# pH_v5_0.net
KiCad netlist of a schematic drawn in EAGLE
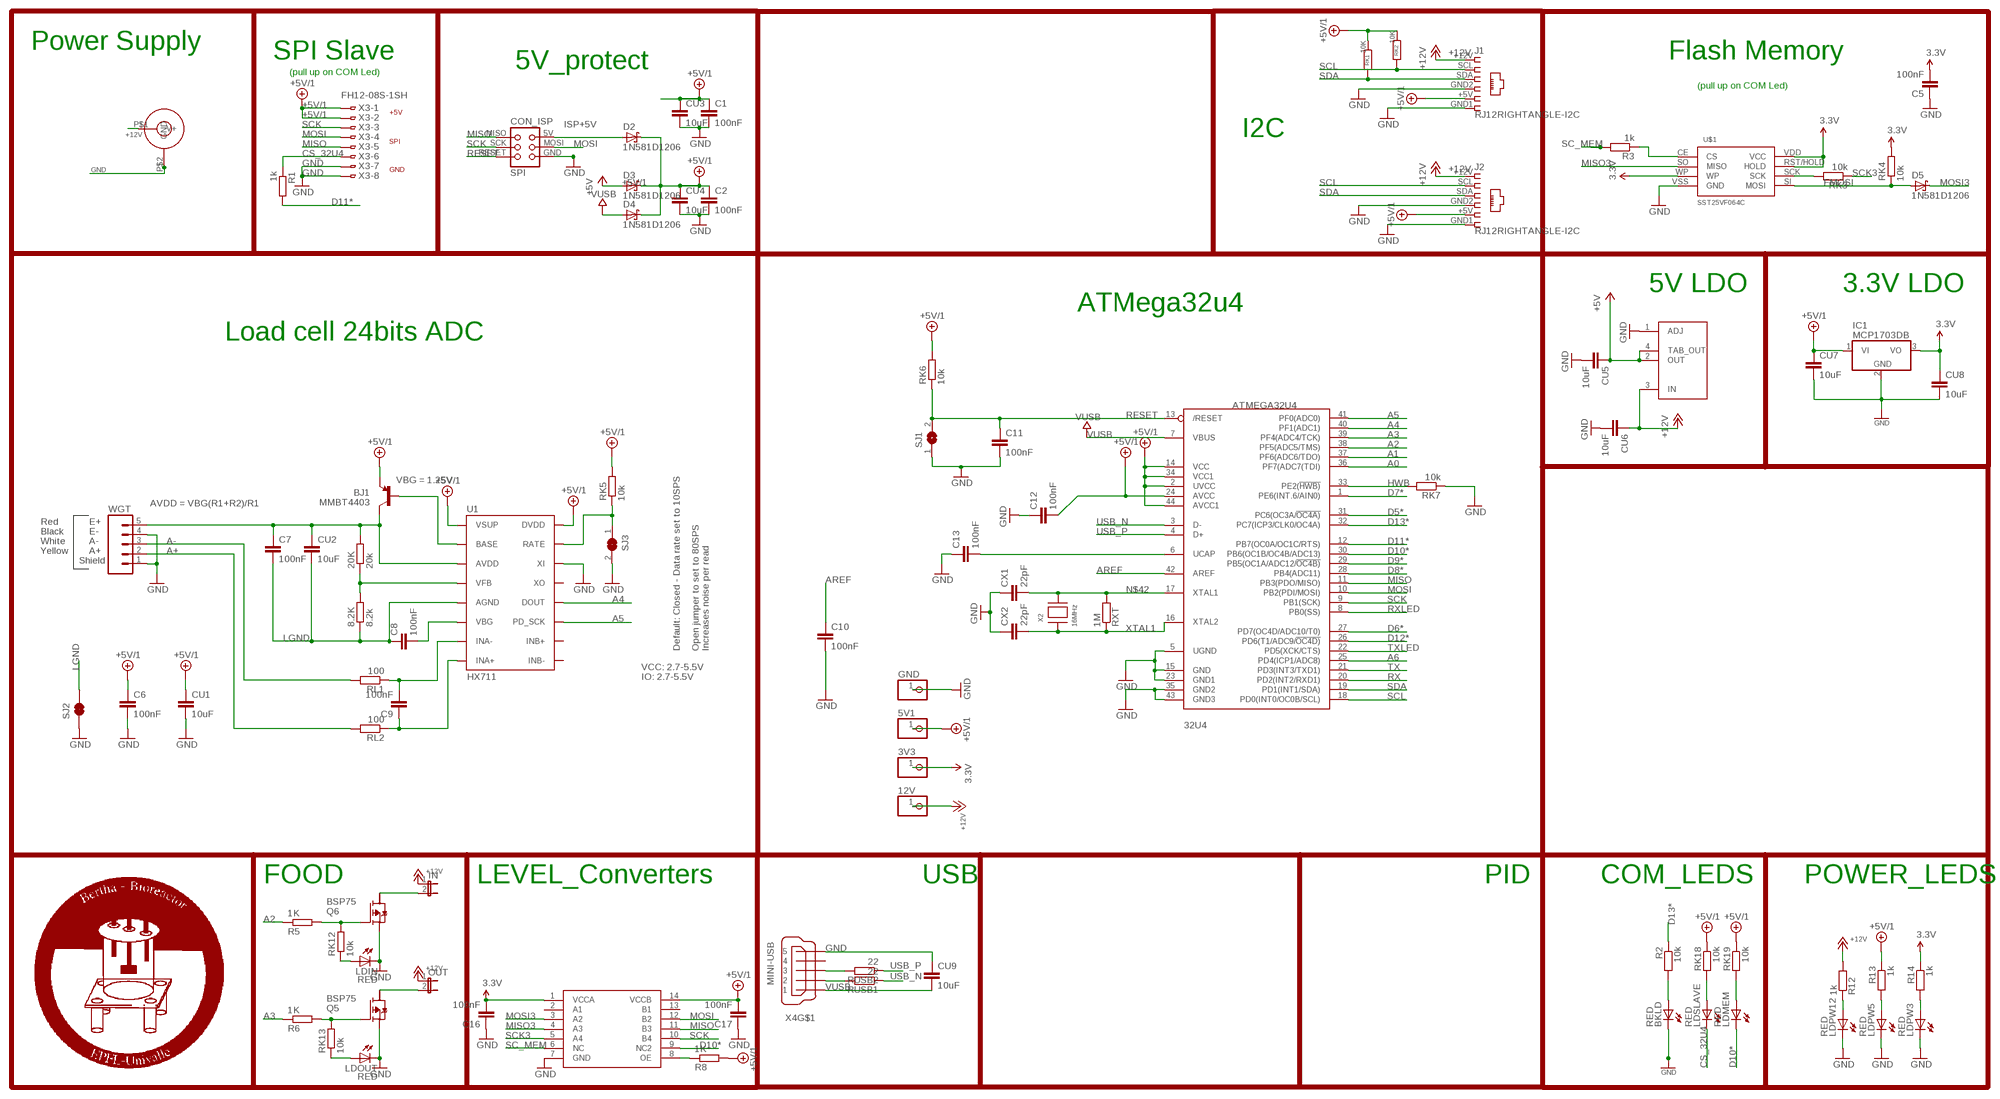
[diagram p0: schematic, sheet 1]

(export (version "E")
  (design (tool "Eeschema 10.0.6"))
  (components
    (comp (ref "3V3")
      (value "PINHD-1X1")
      (footprint "eagle-import:1X01")
      (libsource (lib "eagle-import") (part "PINHD-1X1"))
    )
    (comp (ref "5V1")
      (value "PINHD-1X1")
      (footprint "eagle-import:1X01")
      (libsource (lib "eagle-import") (part "PINHD-1X1"))
    )
    (comp (ref "8.2K")
      (value "8.2k")
      (footprint "eagle-import:M0805")
      (libsource (lib "eagle-import") (part "resistor_R-EU_M0805"))
    )
    (comp (ref "12V")
      (value "PINHD-1X1")
      (footprint "eagle-import:1X01")
      (libsource (lib "eagle-import") (part "PINHD-1X1"))
    )
    (comp (ref "20K")
      (value "20k")
      (footprint "eagle-import:M0805")
      (libsource (lib "eagle-import") (part "resistor_R-EU_M0805"))
    )
    (comp (ref "32U4")
      (value "ATMEGA32U4")
      (footprint "eagle-import:TQFP44")
      (libsource (lib "eagle-import") (part "ATMEGA32U4-AU"))
    )
    (comp (ref "BJ1")
      (value "MMBT4403")
      (footprint "eagle-import:SOT23-3")
      (libsource (lib "eagle-import") (part "TRANSISTOR_PNPMMBT4403"))
    )
    (comp (ref "BKLD")
      (value "RED")
      (footprint "eagle-import:CHIP-LED0805")
      (libsource (lib "eagle-import") (part "LEDCHIP-LED0805"))
    )
    (comp (ref "C1")
      (value "100nF")
      (footprint "eagle-import:C1206")
      (libsource (lib "eagle-import") (part "C-EUC1206"))
    )
    (comp (ref "C2")
      (value "100nF")
      (footprint "eagle-import:C1206")
      (libsource (lib "eagle-import") (part "C-EUC1206"))
    )
    (comp (ref "C5")
      (value "100nF")
      (footprint "eagle-import:C1206")
      (libsource (lib "eagle-import") (part "C-EUC1206"))
    )
    (comp (ref "C6")
      (value "100nF")
      (footprint "eagle-import:C1206")
      (libsource (lib "eagle-import") (part "C-EUC1206"))
    )
    (comp (ref "C7")
      (value "100nF")
      (footprint "eagle-import:C1206")
      (libsource (lib "eagle-import") (part "C-EUC1206"))
    )
    (comp (ref "C8")
      (value "100nF")
      (footprint "eagle-import:C1206")
      (libsource (lib "eagle-import") (part "C-EUC1206"))
    )
    (comp (ref "C9")
      (value "100nF")
      (footprint "eagle-import:C1206")
      (libsource (lib "eagle-import") (part "C-EUC1206"))
    )
    (comp (ref "C10")
      (value "100nF")
      (footprint "eagle-import:C1206")
      (libsource (lib "eagle-import") (part "C-EUC1206"))
    )
    (comp (ref "C11")
      (value "100nF")
      (footprint "eagle-import:C1206")
      (libsource (lib "eagle-import") (part "C-EUC1206"))
    )
    (comp (ref "C12")
      (value "100nF")
      (footprint "eagle-import:C1206")
      (libsource (lib "eagle-import") (part "C-EUC1206"))
    )
    (comp (ref "C13")
      (value "100nF")
      (footprint "eagle-import:C1206")
      (libsource (lib "eagle-import") (part "C-EUC1206"))
    )
    (comp (ref "C16")
      (value "100nF")
      (footprint "eagle-import:C1206")
      (libsource (lib "eagle-import") (part "C-EUC1206"))
    )
    (comp (ref "C17")
      (value "100nF")
      (footprint "eagle-import:C1206")
      (libsource (lib "eagle-import") (part "C-EUC1206"))
    )
    (comp (ref "CON1")
      (value "JACK_DC_BARREL")
      (footprint "eagle-import:DC_BARREL")
      (libsource (lib "eagle-import") (part "JACK_DC_BARREL"))
    )
    (comp (ref "CON_ISP")
      (value "SPI")
      (footprint "eagle-import:TC2030-MCP-NL")
      (libsource (lib "eagle-import") (part "TINYISPT"))
    )
    (comp (ref "CU1")
      (value "10uF")
      (footprint "eagle-import:C1206")
      (libsource (lib "eagle-import") (part "C-EUC1206"))
    )
    (comp (ref "CU2")
      (value "10uF")
      (footprint "eagle-import:C1206")
      (libsource (lib "eagle-import") (part "C-EUC1206"))
    )
    (comp (ref "CU3")
      (value "10uF")
      (footprint "eagle-import:C1206")
      (libsource (lib "eagle-import") (part "C-EUC1206"))
    )
    (comp (ref "CU4")
      (value "10uF")
      (footprint "eagle-import:C1206")
      (libsource (lib "eagle-import") (part "C-EUC1206"))
    )
    (comp (ref "CU5")
      (value "10uF")
      (footprint "eagle-import:C1206")
      (libsource (lib "eagle-import") (part "C-EUC1206"))
    )
    (comp (ref "CU6")
      (value "10uF")
      (footprint "eagle-import:C1206")
      (libsource (lib "eagle-import") (part "C-EUC1206"))
    )
    (comp (ref "CU7")
      (value "10uF")
      (footprint "eagle-import:C1206")
      (libsource (lib "eagle-import") (part "C-EUC1206"))
    )
    (comp (ref "CU8")
      (value "10uF")
      (footprint "eagle-import:C1206")
      (libsource (lib "eagle-import") (part "C-EUC1206"))
    )
    (comp (ref "CU9")
      (value "10uF")
      (footprint "eagle-import:C1206")
      (libsource (lib "eagle-import") (part "C-EUC1206"))
    )
    (comp (ref "CX1")
      (value "22pF")
      (footprint "eagle-import:C1206")
      (libsource (lib "eagle-import") (part "C-EUC1206"))
    )
    (comp (ref "CX2")
      (value "22pF")
      (footprint "eagle-import:C1206")
      (libsource (lib "eagle-import") (part "C-EUC1206"))
    )
    (comp (ref "D2")
      (value "1N581D1206")
      (footprint "eagle-import:LED-1206")
      (libsource (lib "eagle-import") (part "1N581D1206"))
    )
    (comp (ref "D3")
      (value "1N581D1206")
      (footprint "eagle-import:LED-1206")
      (libsource (lib "eagle-import") (part "1N581D1206"))
    )
    (comp (ref "D4")
      (value "1N581D1206")
      (footprint "eagle-import:LED-1206")
      (libsource (lib "eagle-import") (part "1N581D1206"))
    )
    (comp (ref "D5")
      (value "1N581D1206")
      (footprint "eagle-import:LED-1206")
      (libsource (lib "eagle-import") (part "1N581D1206"))
    )
    (comp (ref "GND")
      (value "PINHD-1X1")
      (footprint "eagle-import:1X01")
      (libsource (lib "eagle-import") (part "PINHD-1X1"))
    )
    (comp (ref "IC1")
      (value "MCP1703DB")
      (footprint "eagle-import:SOT223")
      (libsource (lib "eagle-import") (part "MCP1703DB"))
    )
    (comp (ref "IN")
      (value "JP1E")
      (footprint "eagle-import:JP1")
      (libsource (lib "eagle-import") (part "JP1E"))
    )
    (comp (ref "J1")
      (value "RJ12RIGHTANGLE-I2C")
      (footprint "eagle-import:RJ12-RIGHTANGLE-I2C")
      (libsource (lib "eagle-import") (part "RJ12RIGHTANGLE-I2C"))
    )
    (comp (ref "J2")
      (value "RJ12RIGHTANGLE-I2C")
      (footprint "eagle-import:RJ12-RIGHTANGLE-I2C")
      (libsource (lib "eagle-import") (part "RJ12RIGHTANGLE-I2C"))
    )
    (comp (ref "LDIN")
      (value "RED")
      (footprint "eagle-import:CHIP-LED0805")
      (libsource (lib "eagle-import") (part "LEDCHIP-LED0805"))
    )
    (comp (ref "LDMEM")
      (value "RED")
      (footprint "eagle-import:CHIP-LED0805")
      (libsource (lib "eagle-import") (part "LEDCHIP-LED0805"))
    )
    (comp (ref "LDOUT")
      (value "RED")
      (footprint "eagle-import:CHIP-LED0805")
      (libsource (lib "eagle-import") (part "LEDCHIP-LED0805"))
    )
    (comp (ref "LDPW3")
      (value "RED")
      (footprint "eagle-import:CHIP-LED0805")
      (libsource (lib "eagle-import") (part "LEDCHIP-LED0805"))
    )
    (comp (ref "LDPW5")
      (value "RED")
      (footprint "eagle-import:CHIP-LED0805")
      (libsource (lib "eagle-import") (part "LEDCHIP-LED0805"))
    )
    (comp (ref "LDPW12")
      (value "RED")
      (footprint "eagle-import:CHIP-LED0805")
      (libsource (lib "eagle-import") (part "LEDCHIP-LED0805"))
    )
    (comp (ref "LDSLAVE")
      (value "RED")
      (footprint "eagle-import:CHIP-LED0805")
      (libsource (lib "eagle-import") (part "LEDCHIP-LED0805"))
    )
    (comp (ref "OUT")
      (value "JP1E")
      (footprint "eagle-import:JP1")
      (libsource (lib "eagle-import") (part "JP1E"))
    )
    (comp (ref "Q5")
      (value "BSP75")
      (footprint "eagle-import:PG-SOT-223")
      (libsource (lib "eagle-import") (part "BSP613P"))
    )
    (comp (ref "Q6")
      (value "BSP75")
      (footprint "eagle-import:PG-SOT-223")
      (libsource (lib "eagle-import") (part "BSP613P"))
    )
    (comp (ref "R1")
      (value "1k")
      (footprint "eagle-import:R0805")
      (libsource (lib "eagle-import") (part "R-EU_R0805"))
    )
    (comp (ref "R2")
      (value "10k")
      (footprint "eagle-import:R0805")
      (libsource (lib "eagle-import") (part "R-EU_R0805"))
    )
    (comp (ref "R3")
      (value "1k")
      (footprint "eagle-import:R0805")
      (libsource (lib "eagle-import") (part "R-EU_R0805"))
    )
    (comp (ref "R5")
      (value "1K")
      (footprint "eagle-import:R0805")
      (libsource (lib "eagle-import") (part "R-EU_R0805"))
    )
    (comp (ref "R6")
      (value "1K")
      (footprint "eagle-import:R0805")
      (libsource (lib "eagle-import") (part "R-EU_R0805"))
    )
    (comp (ref "R8")
      (value "1K")
      (footprint "eagle-import:R0805")
      (libsource (lib "eagle-import") (part "R-EU_R0805"))
    )
    (comp (ref "R12")
      (value "1k")
      (footprint "eagle-import:R0805")
      (libsource (lib "eagle-import") (part "R-EU_R0805"))
    )
    (comp (ref "R13")
      (value "1k")
      (footprint "eagle-import:R0805")
      (libsource (lib "eagle-import") (part "resistor_R-EU_R0805"))
    )
    (comp (ref "R14")
      (value "1k")
      (footprint "eagle-import:R0805")
      (libsource (lib "eagle-import") (part "resistor_R-EU_R0805"))
    )
    (comp (ref "RK1")
      (value "10K")
      (footprint "eagle-import:M0805")
      (libsource (lib "eagle-import") (part "resistor_R-EU_M0805"))
    )
    (comp (ref "RK2")
      (value "10K")
      (footprint "eagle-import:M0805")
      (libsource (lib "eagle-import") (part "resistor_R-EU_M0805"))
    )
    (comp (ref "RK3")
      (value "10k")
      (footprint "eagle-import:R0805")
      (libsource (lib "eagle-import") (part "R-EU_R0805"))
    )
    (comp (ref "RK4")
      (value "10k")
      (footprint "eagle-import:R0805")
      (libsource (lib "eagle-import") (part "R-EU_R0805"))
    )
    (comp (ref "RK5")
      (value "10k")
      (footprint "eagle-import:M0805")
      (libsource (lib "eagle-import") (part "resistor_R-EU_M0805"))
    )
    (comp (ref "RK6")
      (value "10k")
      (footprint "eagle-import:M0805")
      (libsource (lib "eagle-import") (part "resistor_R-EU_M0805"))
    )
    (comp (ref "RK7")
      (value "10k")
      (footprint "eagle-import:M0805")
      (libsource (lib "eagle-import") (part "resistor_R-EU_M0805"))
    )
    (comp (ref "RK12")
      (value "10k")
      (footprint "eagle-import:R0805")
      (libsource (lib "eagle-import") (part "R-EU_R0805"))
    )
    (comp (ref "RK13")
      (value "10k")
      (footprint "eagle-import:R0805")
      (libsource (lib "eagle-import") (part "R-EU_R0805"))
    )
    (comp (ref "RK18")
      (value "10k")
      (footprint "eagle-import:R0805")
      (libsource (lib "eagle-import") (part "R-EU_R0805"))
    )
    (comp (ref "RK19")
      (value "10k")
      (footprint "eagle-import:R0805")
      (libsource (lib "eagle-import") (part "R-EU_R0805"))
    )
    (comp (ref "RL1")
      (value "100")
      (footprint "eagle-import:M0805")
      (libsource (lib "eagle-import") (part "resistor_R-EU_M0805"))
    )
    (comp (ref "RL2")
      (value "100")
      (footprint "eagle-import:M0805")
      (libsource (lib "eagle-import") (part "resistor_R-EU_M0805"))
    )
    (comp (ref "RUSB1")
      (value "22")
      (footprint "eagle-import:M1206")
      (libsource (lib "eagle-import") (part "resistor_R-EU_M1206"))
    )
    (comp (ref "RUSB2")
      (value "22")
      (footprint "eagle-import:M1206")
      (libsource (lib "eagle-import") (part "resistor_R-EU_M1206"))
    )
    (comp (ref "RXT")
      (value "1M")
      (footprint "eagle-import:R0805")
      (libsource (lib "eagle-import") (part "R-EU_R0805"))
    )
    (comp (ref "SJ1") (value "SJ") (footprint "eagle-import:SJ") (libsource (lib "eagle-import") (part "SJ")))
    (comp (ref "SJ2")
      (value "JUMPER-PAD-2-NC_BY_TRACE")
      (footprint "eagle-import:PAD-JUMPER-2-NC_BY_TRACE_YES_SILK")
      (libsource (lib "eagle-import") (part "JUMPER-PAD-2-NC_BY_TRACE"))
    )
    (comp (ref "SJ3") (value "SJ") (footprint "eagle-import:SJ") (libsource (lib "eagle-import") (part "SJ")))
    (comp (ref "U$1")
      (value "SST25VF064C")
      (footprint "eagle-import:SOIC_8-LEAD")
      (libsource (lib "eagle-import") (part "SST25VF064C"))
    )
    (comp (ref "U$2")
      (value "NCP1117LPST50T3G")
      (footprint "eagle-import:SOT223")
      (libsource (lib "eagle-import") (part "NCP1117LPST50T3G"))
    )
    (comp (ref "U$6")
      (value "TXB0104")
      (footprint "eagle-import:SO14")
      (libsource (lib "eagle-import") (part "TXB0104"))
    )
    (comp (ref "U1")
      (value "HX711")
      (footprint "eagle-import:SO16")
      (libsource (lib "eagle-import") (part "HX711HX711"))
    )
    (comp (ref "WGT")
      (value "M05PTH")
      (footprint "eagle-import:1X05")
      (libsource (lib "eagle-import") (part "M05PTH"))
    )
    (comp (ref "X2")
      (value "16MHz")
      (footprint "eagle-import:NX6035")
      (libsource (lib "eagle-import") (part "XTALNX6035"))
    )
    (comp (ref "X3")
      (value "FH12-08S-1SH")
      (footprint "eagle-import:FH12-08S-1SH")
      (libsource (lib "eagle-import") (part "FH12-08S-1SH"))
    )
    (comp (ref "X4")
      (value "MINI-USB")
      (footprint "eagle-import:32005-201")
      (libsource (lib "eagle-import") (part "MINI-USB-SCHIELD-32005-201"))
    )
  )
  (nets
    (net (code "1") (name "+5V") (class "Default")
      (node (ref "CU5") (pin "1") (pinfunction "1_1") (pintype "passive"))
      (node (ref "D3") (pin "A") (pinfunction "A_A") (pintype "passive"))
      (node (ref "U$2") (pin "2") (pinfunction "OUT_2") (pintype "bidirectional"))
      (node (ref "U$2") (pin "4") (pinfunction "TAB_OUT_4") (pintype "bidirectional"))
    )
    (net (code "2") (name "+5V{slash}1") (class "Default")
      (node (ref "32U4") (pin "14") (pinfunction "VCC_14") (pintype "bidirectional"))
      (node (ref "32U4") (pin "2") (pinfunction "UVCC_2") (pintype "bidirectional"))
      (node (ref "32U4") (pin "24") (pinfunction "AVCC_24") (pintype "bidirectional"))
      (node (ref "32U4") (pin "34") (pinfunction "VCC1_34") (pintype "bidirectional"))
      (node (ref "32U4") (pin "44") (pinfunction "AVCC1_44") (pintype "bidirectional"))
      (node (ref "5V1") (pin "1") (pinfunction "1_1") (pintype "passive"))
      (node (ref "BJ1") (pin "2") (pinfunction "E_2") (pintype "passive"))
      (node (ref "C1") (pin "1") (pinfunction "1_1") (pintype "passive"))
      (node (ref "C12") (pin "2") (pinfunction "2_2") (pintype "passive"))
      (node (ref "C17") (pin "2") (pinfunction "2_2") (pintype "passive"))
      (node (ref "C2") (pin "1") (pinfunction "1_1") (pintype "passive"))
      (node (ref "C6") (pin "1") (pinfunction "1_1") (pintype "passive"))
      (node (ref "CU1") (pin "1") (pinfunction "1_1") (pintype "passive"))
      (node (ref "CU3") (pin "1") (pinfunction "1_1") (pintype "passive"))
      (node (ref "CU4") (pin "1") (pinfunction "1_1") (pintype "passive"))
      (node (ref "CU7") (pin "1") (pinfunction "1_1") (pintype "passive"))
      (node (ref "D2") (pin "C") (pinfunction "C_C") (pintype "passive"))
      (node (ref "D3") (pin "C") (pinfunction "C_C") (pintype "passive"))
      (node (ref "D4") (pin "C") (pinfunction "C_C") (pintype "passive"))
      (node (ref "IC1") (pin "1") (pinfunction "VI_1") (pintype "input"))
      (node (ref "J1") (pin "+5V") (pinfunction "5_+5V") (pintype "power_in"))
      (node (ref "J2") (pin "+5V") (pinfunction "5_+5V") (pintype "power_in"))
      (node (ref "R13") (pin "1") (pinfunction "1_1") (pintype "passive"))
      (node (ref "R8") (pin "2") (pinfunction "2_2") (pintype "passive"))
      (node (ref "RK1") (pin "1") (pinfunction "1_1") (pintype "passive"))
      (node (ref "RK18") (pin "1") (pinfunction "1_1") (pintype "passive"))
      (node (ref "RK19") (pin "1") (pinfunction "1_1") (pintype "passive"))
      (node (ref "RK2") (pin "1") (pinfunction "1_1") (pintype "passive"))
      (node (ref "RK5") (pin "2") (pinfunction "2_2") (pintype "passive"))
      (node (ref "RK6") (pin "2") (pinfunction "2_2") (pintype "passive"))
      (node (ref "U$6") (pin "14") (pinfunction "VCCB_14") (pintype "bidirectional"))
      (node (ref "U1") (pin "1") (pinfunction "VSUP_1") (pintype "bidirectional"))
      (node (ref "U1") (pin "16") (pinfunction "DVDD_16") (pintype "bidirectional"))
      (node (ref "X3") (pin "1") (pinfunction "1_1") (pintype "passive"))
      (node (ref "X3") (pin "2") (pinfunction "1_2") (pintype "passive"))
    )
    (net (code "3") (name "+12V") (class "Default")
      (node (ref "12V") (pin "1") (pinfunction "1_1") (pintype "passive"))
      (node (ref "CON1") (pin "P$1") (pinfunction "V+_P$1") (pintype "bidirectional"))
      (node (ref "CU6") (pin "1") (pinfunction "1_1") (pintype "passive"))
      (node (ref "IN") (pin "1") (pinfunction "1_1") (pintype "passive"))
      (node (ref "J1") (pin "+12V") (pinfunction "1_+12V") (pintype "power_in"))
      (node (ref "J2") (pin "+12V") (pinfunction "1_+12V") (pintype "power_in"))
      (node (ref "OUT") (pin "1") (pinfunction "1_1") (pintype "passive"))
      (node (ref "R12") (pin "2") (pinfunction "2_2") (pintype "passive"))
      (node (ref "U$2") (pin "3") (pinfunction "IN_3") (pintype "bidirectional"))
    )
    (net (code "4") (name "/A+") (class "Default")
      (node (ref "RL2") (pin "2") (pinfunction "2_2") (pintype "passive"))
      (node (ref "WGT") (pin "2") (pinfunction "2_2") (pintype "passive"))
    )
    (net (code "5") (name "/A-") (class "Default")
      (node (ref "RL1") (pin "2") (pinfunction "2_2") (pintype "passive"))
      (node (ref "WGT") (pin "3") (pinfunction "3_3") (pintype "passive"))
    )
    (net (code "6") (name "/A0") (class "Default")
      (node (ref "32U4") (pin "36") (pinfunction "PF7(ADC7(TDI)_36") (pintype "bidirectional"))
    )
    (net (code "7") (name "/A1") (class "Default")
      (node (ref "32U4") (pin "37") (pinfunction "PF6(ADC6/TDO)_37") (pintype "bidirectional"))
    )
    (net (code "8") (name "/A2") (class "Default")
      (node (ref "32U4") (pin "38") (pinfunction "PF5(ADC5/TMS)_38") (pintype "bidirectional"))
      (node (ref "R5") (pin "1") (pinfunction "1_1") (pintype "passive"))
    )
    (net (code "9") (name "/A3") (class "Default")
      (node (ref "32U4") (pin "39") (pinfunction "PF4(ADC4/TCK)_39") (pintype "bidirectional"))
      (node (ref "R6") (pin "1") (pinfunction "1_1") (pintype "passive"))
    )
    (net (code "10") (name "/A4") (class "Default")
      (node (ref "32U4") (pin "40") (pinfunction "PF1(ADC1)_40") (pintype "bidirectional"))
      (node (ref "U1") (pin "12") (pinfunction "DOUT_12") (pintype "bidirectional"))
    )
    (net (code "11") (name "/A5") (class "Default")
      (node (ref "32U4") (pin "41") (pinfunction "PF0(ADC0)_41") (pintype "bidirectional"))
      (node (ref "U1") (pin "11") (pinfunction "PD_SCK_11") (pintype "bidirectional"))
    )
    (net (code "12") (name "/A6") (class "Default")
      (node (ref "32U4") (pin "25") (pinfunction "PD4(ICP1/ADC8)_25") (pintype "bidirectional"))
    )
    (net (code "13") (name "/AREF") (class "Default")
      (node (ref "32U4") (pin "42") (pinfunction "AREF_42") (pintype "bidirectional"))
      (node (ref "C10") (pin "1") (pinfunction "1_1") (pintype "passive"))
    )
    (net (code "14") (name "/CS_32U4") (class "Default")
      (node (ref "LDSLAVE") (pin "C") (pinfunction "C_C") (pintype "passive"))
      (node (ref "R1") (pin "1") (pinfunction "1_1") (pintype "passive"))
      (node (ref "X3") (pin "6") (pinfunction "1_6") (pintype "passive"))
    )
    (net (code "15") (name "/D5*") (class "Default")
      (node (ref "32U4") (pin "31") (pinfunction "PC6(OC3A/~{OC4A})_31") (pintype "bidirectional"))
    )
    (net (code "16") (name "/D6*") (class "Default")
      (node (ref "32U4") (pin "27") (pinfunction "PD7(OC4D/ADC10/T0)_27") (pintype "bidirectional"))
    )
    (net (code "17") (name "/D7*") (class "Default")
      (node (ref "32U4") (pin "1") (pinfunction "PE6(INT.6/AIN0)_1") (pintype "bidirectional"))
    )
    (net (code "18") (name "/D8*") (class "Default")
      (node (ref "32U4") (pin "28") (pinfunction "PB4(ADC11)_28") (pintype "bidirectional"))
    )
    (net (code "19") (name "/D9*") (class "Default")
      (node (ref "32U4") (pin "29") (pinfunction "PB5(OC1A/ADC12/~{OC4B})_29") (pintype "bidirectional"))
    )
    (net (code "20") (name "/D10*") (class "Default")
      (node (ref "32U4") (pin "30") (pinfunction "PB6(OC1B/OC4B/ADC13)_30") (pintype "bidirectional"))
      (node (ref "LDMEM") (pin "C") (pinfunction "C_C") (pintype "passive"))
      (node (ref "U$6") (pin "9") (pinfunction "NC2_9") (pintype "bidirectional"))
    )
    (net (code "21") (name "/D11*") (class "Default")
      (node (ref "32U4") (pin "12") (pinfunction "PB7(OC0A/OC1C/RTS)_12") (pintype "bidirectional"))
      (node (ref "R1") (pin "2") (pinfunction "2_2") (pintype "passive"))
    )
    (net (code "22") (name "/D12*") (class "Default")
      (node (ref "32U4") (pin "26") (pinfunction "PD6(T1/ADC9/~{OC4D})_26") (pintype "bidirectional"))
    )
    (net (code "23") (name "/D13*") (class "Default")
      (node (ref "32U4") (pin "32") (pinfunction "PC7(ICP3/CLK0/OC4A)_32") (pintype "bidirectional"))
      (node (ref "R2") (pin "1") (pinfunction "1_1") (pintype "passive"))
    )
    (net (code "24") (name "/FMOSI") (class "Default")
      (node (ref "D5") (pin "A") (pinfunction "A_A") (pintype "passive"))
      (node (ref "RK4") (pin "1") (pinfunction "1_1") (pintype "passive"))
      (node (ref "U$1") (pin "SI") (pinfunction "MOSI_SI") (pintype "bidirectional"))
    )
    (net (code "25") (name "/HWB") (class "Default")
      (node (ref "32U4") (pin "33") (pinfunction "PE2(~{HWB})_33") (pintype "bidirectional"))
      (node (ref "RK7") (pin "2") (pinfunction "2_2") (pintype "passive"))
    )
    (net (code "26") (name "/ISP+5V") (class "Default")
      (node (ref "CON_ISP") (pin "5V") (pinfunction "VCC_5V") (pintype "passive"))
      (node (ref "D2") (pin "A") (pinfunction "A_A") (pintype "passive"))
    )
    (net (code "27") (name "/LGND") (class "Default")
      (node (ref "8.2K") (pin "1") (pinfunction "1_1") (pintype "passive"))
      (node (ref "C7") (pin "2") (pinfunction "2_2") (pintype "passive"))
      (node (ref "C8") (pin "1") (pinfunction "1_1") (pintype "passive"))
      (node (ref "CU2") (pin "2") (pinfunction "2_2") (pintype "passive"))
      (node (ref "SJ2") (pin "2") (pinfunction "2_2") (pintype "passive"))
      (node (ref "U1") (pin "5") (pinfunction "AGND_5") (pintype "bidirectional"))
    )
    (net (code "28") (name "/MISO") (class "Default")
      (node (ref "32U4") (pin "11") (pinfunction "PB3(PDO/MISO)_11") (pintype "bidirectional"))
      (node (ref "CON_ISP") (pin "MISO") (pinfunction "MISO_MISO") (pintype "passive"))
      (node (ref "U$6") (pin "11") (pinfunction "B3_11") (pintype "bidirectional"))
      (node (ref "X3") (pin "5") (pinfunction "1_5") (pintype "passive"))
    )
    (net (code "29") (name "/MISO3") (class "Default")
      (node (ref "U$1") (pin "SO") (pinfunction "MISO_SO") (pintype "bidirectional"))
      (node (ref "U$6") (pin "4") (pinfunction "A3_4") (pintype "bidirectional"))
    )
    (net (code "30") (name "/MOSI") (class "Default")
      (node (ref "32U4") (pin "10") (pinfunction "PB2(PDI/MOSI)_10") (pintype "bidirectional"))
      (node (ref "CON_ISP") (pin "MOSI") (pinfunction "MOSI_MOSI") (pintype "passive"))
      (node (ref "U$6") (pin "12") (pinfunction "B2_12") (pintype "bidirectional"))
      (node (ref "X3") (pin "4") (pinfunction "1_4") (pintype "passive"))
    )
    (net (code "31") (name "/MOSI3") (class "Default")
      (node (ref "D5") (pin "C") (pinfunction "C_C") (pintype "passive"))
      (node (ref "U$6") (pin "3") (pinfunction "A2_3") (pintype "bidirectional"))
    )
    (net (code "32") (name "/N$42") (class "Default")
      (node (ref "32U4") (pin "17") (pinfunction "XTAL1_17") (pintype "bidirectional"))
      (node (ref "CX1") (pin "2") (pinfunction "2_2") (pintype "passive"))
      (node (ref "RXT") (pin "2") (pinfunction "2_2") (pintype "passive"))
      (node (ref "X2") (pin "P$2") (pinfunction "P$2_P$2") (pintype "bidirectional"))
    )
    (net (code "33") (name "/RESET") (class "Default")
      (node (ref "32U4") (pin "13") (pinfunction "/RESET_13") (pintype "bidirectional"))
      (node (ref "C11") (pin "1") (pinfunction "1_1") (pintype "passive"))
      (node (ref "CON_ISP") (pin "RESET") (pinfunction "RESET_RESET") (pintype "passive"))
      (node (ref "RK6") (pin "1") (pinfunction "1_1") (pintype "passive"))
      (node (ref "SJ1") (pin "2") (pinfunction "2_2") (pintype "passive"))
    )
    (net (code "34") (name "/RX") (class "Default")
      (node (ref "32U4") (pin "20") (pinfunction "PD2(INT2/RXD1)_20") (pintype "bidirectional"))
    )
    (net (code "35") (name "/RXLED") (class "Default")
      (node (ref "32U4") (pin "8") (pinfunction "PB0(SS)_8") (pintype "bidirectional"))
    )
    (net (code "36") (name "/SCK") (class "Default")
      (node (ref "32U4") (pin "9") (pinfunction "PB1(SCK)_9") (pintype "bidirectional"))
      (node (ref "CON_ISP") (pin "SCK") (pinfunction "SCK_SCK") (pintype "passive"))
      (node (ref "U$6") (pin "10") (pinfunction "B4_10") (pintype "bidirectional"))
      (node (ref "X3") (pin "3") (pinfunction "1_3") (pintype "passive"))
    )
    (net (code "37") (name "/SCK3") (class "Default")
      (node (ref "RK3") (pin "1") (pinfunction "1_1") (pintype "passive"))
      (node (ref "U$6") (pin "5") (pinfunction "A4_5") (pintype "bidirectional"))
    )
    (net (code "38") (name "/SCL") (class "Default")
      (node (ref "32U4") (pin "18") (pinfunction "PD0(INT0/OC0B/SCL)_18") (pintype "bidirectional"))
      (node (ref "J1") (pin "SCL") (pinfunction "2_SCL") (pintype "bidirectional"))
      (node (ref "J2") (pin "SCL") (pinfunction "2_SCL") (pintype "bidirectional"))
      (node (ref "RK2") (pin "2") (pinfunction "2_2") (pintype "passive"))
    )
    (net (code "39") (name "/SC_MEM") (class "Default")
      (node (ref "R3") (pin "2") (pinfunction "2_2") (pintype "passive"))
      (node (ref "U$6") (pin "6") (pinfunction "NC_6") (pintype "bidirectional"))
    )
    (net (code "40") (name "/SDA") (class "Default")
      (node (ref "32U4") (pin "19") (pinfunction "PD1(INT1/SDA)_19") (pintype "bidirectional"))
      (node (ref "J1") (pin "SDA") (pinfunction "3_SDA") (pintype "bidirectional"))
      (node (ref "J2") (pin "SDA") (pinfunction "3_SDA") (pintype "bidirectional"))
      (node (ref "RK1") (pin "2") (pinfunction "2_2") (pintype "passive"))
    )
    (net (code "41") (name "/TX") (class "Default")
      (node (ref "32U4") (pin "21") (pinfunction "PD3(INT3/TXD1)_21") (pintype "bidirectional"))
    )
    (net (code "42") (name "/TXLED") (class "Default")
      (node (ref "32U4") (pin "22") (pinfunction "PD5(XCK/CTS)_22") (pintype "bidirectional"))
    )
    (net (code "43") (name "/USB_N") (class "Default")
      (node (ref "32U4") (pin "3") (pinfunction "D-_3") (pintype "bidirectional"))
      (node (ref "RUSB1") (pin "1") (pinfunction "1_1") (pintype "passive"))
    )
    (net (code "44") (name "/USB_P") (class "Default")
      (node (ref "32U4") (pin "4") (pinfunction "D+_4") (pintype "bidirectional"))
      (node (ref "RUSB2") (pin "1") (pinfunction "1_1") (pintype "passive"))
    )
    (net (code "45") (name "/XTAL1") (class "Default")
      (node (ref "32U4") (pin "16") (pinfunction "XTAL2_16") (pintype "bidirectional"))
      (node (ref "CX2") (pin "2") (pinfunction "2_2") (pintype "passive"))
      (node (ref "RXT") (pin "1") (pinfunction "1_1") (pintype "passive"))
      (node (ref "X2") (pin "P$1") (pinfunction "P$1_P$1") (pintype "bidirectional"))
    )
    (net (code "46") (name "3.3V") (class "Default")
      (node (ref "3V3") (pin "1") (pinfunction "1_1") (pintype "passive"))
      (node (ref "C16") (pin "2") (pinfunction "2_2") (pintype "passive"))
      (node (ref "C5") (pin "2") (pinfunction "2_2") (pintype "passive"))
      (node (ref "CU8") (pin "1") (pinfunction "1_1") (pintype "passive"))
      (node (ref "IC1") (pin "3") (pinfunction "VO_3") (pintype "passive"))
      (node (ref "R14") (pin "1") (pinfunction "1_1") (pintype "passive"))
      (node (ref "RK4") (pin "2") (pinfunction "2_2") (pintype "passive"))
      (node (ref "U$1") (pin "RST/HOLD") (pinfunction "HOLD_RST/HOLD") (pintype "bidirectional"))
      (node (ref "U$1") (pin "VDD") (pinfunction "VCC_VDD") (pintype "bidirectional"))
      (node (ref "U$1") (pin "WP") (pinfunction "WP_WP") (pintype "bidirectional"))
      (node (ref "U$6") (pin "1") (pinfunction "VCCA_1") (pintype "bidirectional"))
    )
    (net (code "47") (name "GND") (class "Default")
      (node (ref "32U4") (pin "15") (pinfunction "GND_15") (pintype "bidirectional"))
      (node (ref "32U4") (pin "23") (pinfunction "GND1_23") (pintype "bidirectional"))
      (node (ref "32U4") (pin "35") (pinfunction "GND2_35") (pintype "bidirectional"))
      (node (ref "32U4") (pin "43") (pinfunction "GND3_43") (pintype "bidirectional"))
      (node (ref "32U4") (pin "5") (pinfunction "UGND_5") (pintype "bidirectional"))
      (node (ref "BKLD") (pin "C") (pinfunction "C_C") (pintype "passive"))
      (node (ref "C1") (pin "2") (pinfunction "2_2") (pintype "passive"))
      (node (ref "C10") (pin "2") (pinfunction "2_2") (pintype "passive"))
      (node (ref "C11") (pin "2") (pinfunction "2_2") (pintype "passive"))
      (node (ref "C12") (pin "1") (pinfunction "1_1") (pintype "passive"))
      (node (ref "C13") (pin "1") (pinfunction "1_1") (pintype "passive"))
      (node (ref "C16") (pin "1") (pinfunction "1_1") (pintype "passive"))
      (node (ref "C17") (pin "1") (pinfunction "1_1") (pintype "passive"))
      (node (ref "C2") (pin "2") (pinfunction "2_2") (pintype "passive"))
      (node (ref "C5") (pin "1") (pinfunction "1_1") (pintype "passive"))
      (node (ref "C6") (pin "2") (pinfunction "2_2") (pintype "passive"))
      (node (ref "CON1") (pin "P$2") (pinfunction "GND_P$2") (pintype "bidirectional"))
      (node (ref "CON_ISP") (pin "GND") (pinfunction "GND_GND") (pintype "passive"))
      (node (ref "CU1") (pin "2") (pinfunction "2_2") (pintype "passive"))
      (node (ref "CU3") (pin "2") (pinfunction "2_2") (pintype "passive"))
      (node (ref "CU4") (pin "2") (pinfunction "2_2") (pintype "passive"))
      (node (ref "CU5") (pin "2") (pinfunction "2_2") (pintype "passive"))
      (node (ref "CU6") (pin "2") (pinfunction "2_2") (pintype "passive"))
      (node (ref "CU7") (pin "2") (pinfunction "2_2") (pintype "passive"))
      (node (ref "CU8") (pin "2") (pinfunction "2_2") (pintype "passive"))
      (node (ref "CU9") (pin "1") (pinfunction "1_1") (pintype "passive"))
      (node (ref "CX1") (pin "1") (pinfunction "1_1") (pintype "passive"))
      (node (ref "CX2") (pin "1") (pinfunction "1_1") (pintype "passive"))
      (node (ref "GND") (pin "1") (pinfunction "1_1") (pintype "passive"))
      (node (ref "IC1") (pin "2") (pinfunction "GND_2") (pintype "passive"))
      (node (ref "J1") (pin "GND1") (pinfunction "6_GND1") (pintype "power_in"))
      (node (ref "J1") (pin "GND2") (pinfunction "4_GND2") (pintype "power_in"))
      (node (ref "J2") (pin "GND1") (pinfunction "6_GND1") (pintype "power_in"))
      (node (ref "J2") (pin "GND2") (pinfunction "4_GND2") (pintype "power_in"))
      (node (ref "LDIN") (pin "C") (pinfunction "C_C") (pintype "passive"))
      (node (ref "LDOUT") (pin "C") (pinfunction "C_C") (pintype "passive"))
      (node (ref "LDPW12") (pin "C") (pinfunction "C_C") (pintype "passive"))
      (node (ref "LDPW3") (pin "C") (pinfunction "C_C") (pintype "passive"))
      (node (ref "LDPW5") (pin "C") (pinfunction "C_C") (pintype "passive"))
      (node (ref "Q5") (pin "3") (pinfunction "S_3") (pintype "passive"))
      (node (ref "Q6") (pin "3") (pinfunction "S_3") (pintype "passive"))
      (node (ref "RK7") (pin "1") (pinfunction "1_1") (pintype "passive"))
      (node (ref "SJ1") (pin "1") (pinfunction "1_1") (pintype "passive"))
      (node (ref "SJ2") (pin "1") (pinfunction "1_1") (pintype "passive"))
      (node (ref "SJ3") (pin "2") (pinfunction "2_2") (pintype "passive"))
      (node (ref "U$1") (pin "VSS") (pinfunction "GND_VSS") (pintype "bidirectional"))
      (node (ref "U$2") (pin "1") (pinfunction "ADJ_1") (pintype "bidirectional"))
      (node (ref "U$6") (pin "7") (pinfunction "GND_7") (pintype "bidirectional"))
      (node (ref "U1") (pin "14") (pinfunction "XI_14") (pintype "bidirectional"))
      (node (ref "WGT") (pin "1") (pinfunction "1_1") (pintype "passive"))
      (node (ref "WGT") (pin "4") (pinfunction "4_4") (pintype "passive"))
      (node (ref "X3") (pin "7") (pinfunction "1_7") (pintype "passive"))
      (node (ref "X3") (pin "8") (pinfunction "1_8") (pintype "passive"))
      (node (ref "X4") (pin "5") (pinfunction "5_5") (pintype "passive"))
    )
    (net (code "48") (name "Net-(32U4-UCAP)") (class "Default")
      (node (ref "32U4") (pin "6") (pinfunction "UCAP_6") (pintype "bidirectional"))
      (node (ref "C13") (pin "2") (pinfunction "2_2") (pintype "passive"))
    )
    (net (code "49") (name "Net-(BJ1-B)") (class "Default")
      (node (ref "BJ1") (pin "1") (pinfunction "B_1") (pintype "passive"))
      (node (ref "U1") (pin "2") (pinfunction "BASE_2") (pintype "bidirectional"))
    )
    (net (code "50") (name "Net-(BJ1-C)") (class "Default")
      (node (ref "20K") (pin "2") (pinfunction "2_2") (pintype "passive"))
      (node (ref "BJ1") (pin "3") (pinfunction "C_3") (pintype "passive"))
      (node (ref "C7") (pin "1") (pinfunction "1_1") (pintype "passive"))
      (node (ref "CU2") (pin "1") (pinfunction "1_1") (pintype "passive"))
      (node (ref "U1") (pin "3") (pinfunction "AVDD_3") (pintype "bidirectional"))
      (node (ref "WGT") (pin "5") (pinfunction "5_5") (pintype "passive"))
    )
    (net (code "51") (name "Net-(BKLD-PadA)") (class "Default")
      (node (ref "BKLD") (pin "A") (pinfunction "A_A") (pintype "passive"))
      (node (ref "R2") (pin "2") (pinfunction "2_2") (pintype "passive"))
    )
    (net (code "52") (name "Net-(IN-Pad2)") (class "Default")
      (node (ref "IN") (pin "2") (pinfunction "2_2") (pintype "passive"))
      (node (ref "Q6") (pin "2") (pinfunction "D_2") (pintype "passive"))
    )
    (net (code "53") (name "Net-(LDIN-PadA)") (class "Default")
      (node (ref "LDIN") (pin "A") (pinfunction "A_A") (pintype "passive"))
      (node (ref "RK12") (pin "1") (pinfunction "1_1") (pintype "passive"))
    )
    (net (code "54") (name "Net-(LDMEM-PadA)") (class "Default")
      (node (ref "LDMEM") (pin "A") (pinfunction "A_A") (pintype "passive"))
      (node (ref "RK19") (pin "2") (pinfunction "2_2") (pintype "passive"))
    )
    (net (code "55") (name "Net-(LDOUT-PadA)") (class "Default")
      (node (ref "LDOUT") (pin "A") (pinfunction "A_A") (pintype "passive"))
      (node (ref "RK13") (pin "1") (pinfunction "1_1") (pintype "passive"))
    )
    (net (code "56") (name "Net-(LDPW3-PadA)") (class "Default")
      (node (ref "LDPW3") (pin "A") (pinfunction "A_A") (pintype "passive"))
      (node (ref "R14") (pin "2") (pinfunction "2_2") (pintype "passive"))
    )
    (net (code "57") (name "Net-(LDPW5-PadA)") (class "Default")
      (node (ref "LDPW5") (pin "A") (pinfunction "A_A") (pintype "passive"))
      (node (ref "R13") (pin "2") (pinfunction "2_2") (pintype "passive"))
    )
    (net (code "58") (name "Net-(LDPW12-PadA)") (class "Default")
      (node (ref "LDPW12") (pin "A") (pinfunction "A_A") (pintype "passive"))
      (node (ref "R12") (pin "1") (pinfunction "1_1") (pintype "passive"))
    )
    (net (code "59") (name "Net-(LDSLAVE-PadA)") (class "Default")
      (node (ref "LDSLAVE") (pin "A") (pinfunction "A_A") (pintype "passive"))
      (node (ref "RK18") (pin "2") (pinfunction "2_2") (pintype "passive"))
    )
    (net (code "60") (name "Net-(OUT-Pad2)") (class "Default")
      (node (ref "OUT") (pin "2") (pinfunction "2_2") (pintype "passive"))
      (node (ref "Q5") (pin "2") (pinfunction "D_2") (pintype "passive"))
    )
    (net (code "61") (name "Net-(Q5-G)") (class "Default")
      (node (ref "Q5") (pin "1") (pinfunction "G_1") (pintype "passive"))
      (node (ref "R6") (pin "2") (pinfunction "2_2") (pintype "passive"))
      (node (ref "RK13") (pin "2") (pinfunction "2_2") (pintype "passive"))
    )
    (net (code "62") (name "Net-(Q6-G)") (class "Default")
      (node (ref "Q6") (pin "1") (pinfunction "G_1") (pintype "passive"))
      (node (ref "R5") (pin "2") (pinfunction "2_2") (pintype "passive"))
      (node (ref "RK12") (pin "2") (pinfunction "2_2") (pintype "passive"))
    )
    (net (code "63") (name "Net-(RK3-Pad2)") (class "Default")
      (node (ref "RK3") (pin "2") (pinfunction "2_2") (pintype "passive"))
      (node (ref "U$1") (pin "SCK") (pinfunction "SCK_SCK") (pintype "bidirectional"))
    )
    (net (code "64") (name "Net-(RUSB1-Pad2)") (class "Default")
      (node (ref "RUSB1") (pin "2") (pinfunction "2_2") (pintype "passive"))
      (node (ref "X4") (pin "2") (pinfunction "2_2") (pintype "passive"))
    )
    (net (code "65") (name "Net-(RUSB2-Pad2)") (class "Default")
      (node (ref "RUSB2") (pin "2") (pinfunction "2_2") (pintype "passive"))
      (node (ref "X4") (pin "3") (pinfunction "3_3") (pintype "passive"))
    )
    (net (code "66") (name "Net-(U$1-CS)") (class "Default")
      (node (ref "R3") (pin "1") (pinfunction "1_1") (pintype "passive"))
      (node (ref "U$1") (pin "CE") (pinfunction "CS_CE") (pintype "bidirectional"))
    )
    (net (code "67") (name "Net-(U$6-OE)") (class "Default")
      (node (ref "R8") (pin "1") (pinfunction "1_1") (pintype "passive"))
      (node (ref "U$6") (pin "8") (pinfunction "OE_8") (pintype "bidirectional"))
    )
    (net (code "68") (name "Net-(U1-INA+)") (class "Default")
      (node (ref "C9") (pin "1") (pinfunction "1_1") (pintype "passive"))
      (node (ref "RL2") (pin "1") (pinfunction "1_1") (pintype "passive"))
      (node (ref "U1") (pin "8") (pinfunction "INA+_8") (pintype "bidirectional"))
    )
    (net (code "69") (name "Net-(U1-INA-)") (class "Default")
      (node (ref "C9") (pin "2") (pinfunction "2_2") (pintype "passive"))
      (node (ref "RL1") (pin "1") (pinfunction "1_1") (pintype "passive"))
      (node (ref "U1") (pin "7") (pinfunction "INA-_7") (pintype "bidirectional"))
    )
    (net (code "70") (name "Net-(U1-RATE)") (class "Default")
      (node (ref "RK5") (pin "1") (pinfunction "1_1") (pintype "passive"))
      (node (ref "SJ3") (pin "1") (pinfunction "1_1") (pintype "passive"))
      (node (ref "U1") (pin "15") (pinfunction "RATE_15") (pintype "bidirectional"))
    )
    (net (code "71") (name "Net-(U1-VBG)") (class "Default")
      (node (ref "C8") (pin "2") (pinfunction "2_2") (pintype "passive"))
      (node (ref "U1") (pin "6") (pinfunction "VBG_6") (pintype "bidirectional"))
    )
    (net (code "72") (name "Net-(U1-VFB)") (class "Default")
      (node (ref "20K") (pin "1") (pinfunction "1_1") (pintype "passive"))
      (node (ref "8.2K") (pin "2") (pinfunction "2_2") (pintype "passive"))
      (node (ref "U1") (pin "4") (pinfunction "VFB_4") (pintype "bidirectional"))
    )
    (net (code "73") (name "VUSB") (class "Default")
      (node (ref "32U4") (pin "7") (pinfunction "VBUS_7") (pintype "bidirectional"))
      (node (ref "CU9") (pin "2") (pinfunction "2_2") (pintype "passive"))
      (node (ref "D4") (pin "A") (pinfunction "A_A") (pintype "passive"))
      (node (ref "X4") (pin "1") (pinfunction "1_1") (pintype "passive"))
    )
    (net (code "74") (name "unconnected-(Q5-D-Pad4)") (class "Default")
      (node (ref "Q5") (pin "4") (pinfunction "D_4") (pintype "passive"))
    )
    (net (code "75") (name "unconnected-(Q6-D-Pad4)") (class "Default")
      (node (ref "Q6") (pin "4") (pinfunction "D_4") (pintype "passive"))
    )
    (net (code "76") (name "unconnected-(U$6-A1-Pad2)") (class "Default")
      (node (ref "U$6") (pin "2") (pinfunction "A1_2") (pintype "bidirectional"))
    )
    (net (code "77") (name "unconnected-(U$6-B1-Pad13)") (class "Default")
      (node (ref "U$6") (pin "13") (pinfunction "B1_13") (pintype "bidirectional"))
    )
    (net (code "78") (name "unconnected-(U1-INB+-Pad10)") (class "Default")
      (node (ref "U1") (pin "10") (pinfunction "INB+_10") (pintype "bidirectional"))
    )
    (net (code "79") (name "unconnected-(U1-INB--Pad9)") (class "Default")
      (node (ref "U1") (pin "9") (pinfunction "INB-_9") (pintype "bidirectional"))
    )
    (net (code "80") (name "unconnected-(U1-XO-Pad13)") (class "Default")
      (node (ref "U1") (pin "13") (pinfunction "XO_13") (pintype "bidirectional"))
    )
    (net (code "81") (name "unconnected-(X4-Pad4)") (class "Default")
      (node (ref "X4") (pin "4") (pinfunction "4_4") (pintype "passive"))
    )
  )
)
